# EVK-NORA-B2_SCHEM_0004_SWITCH_Memory.net
KiCad netlist of a schematic drawn in Altium Designer
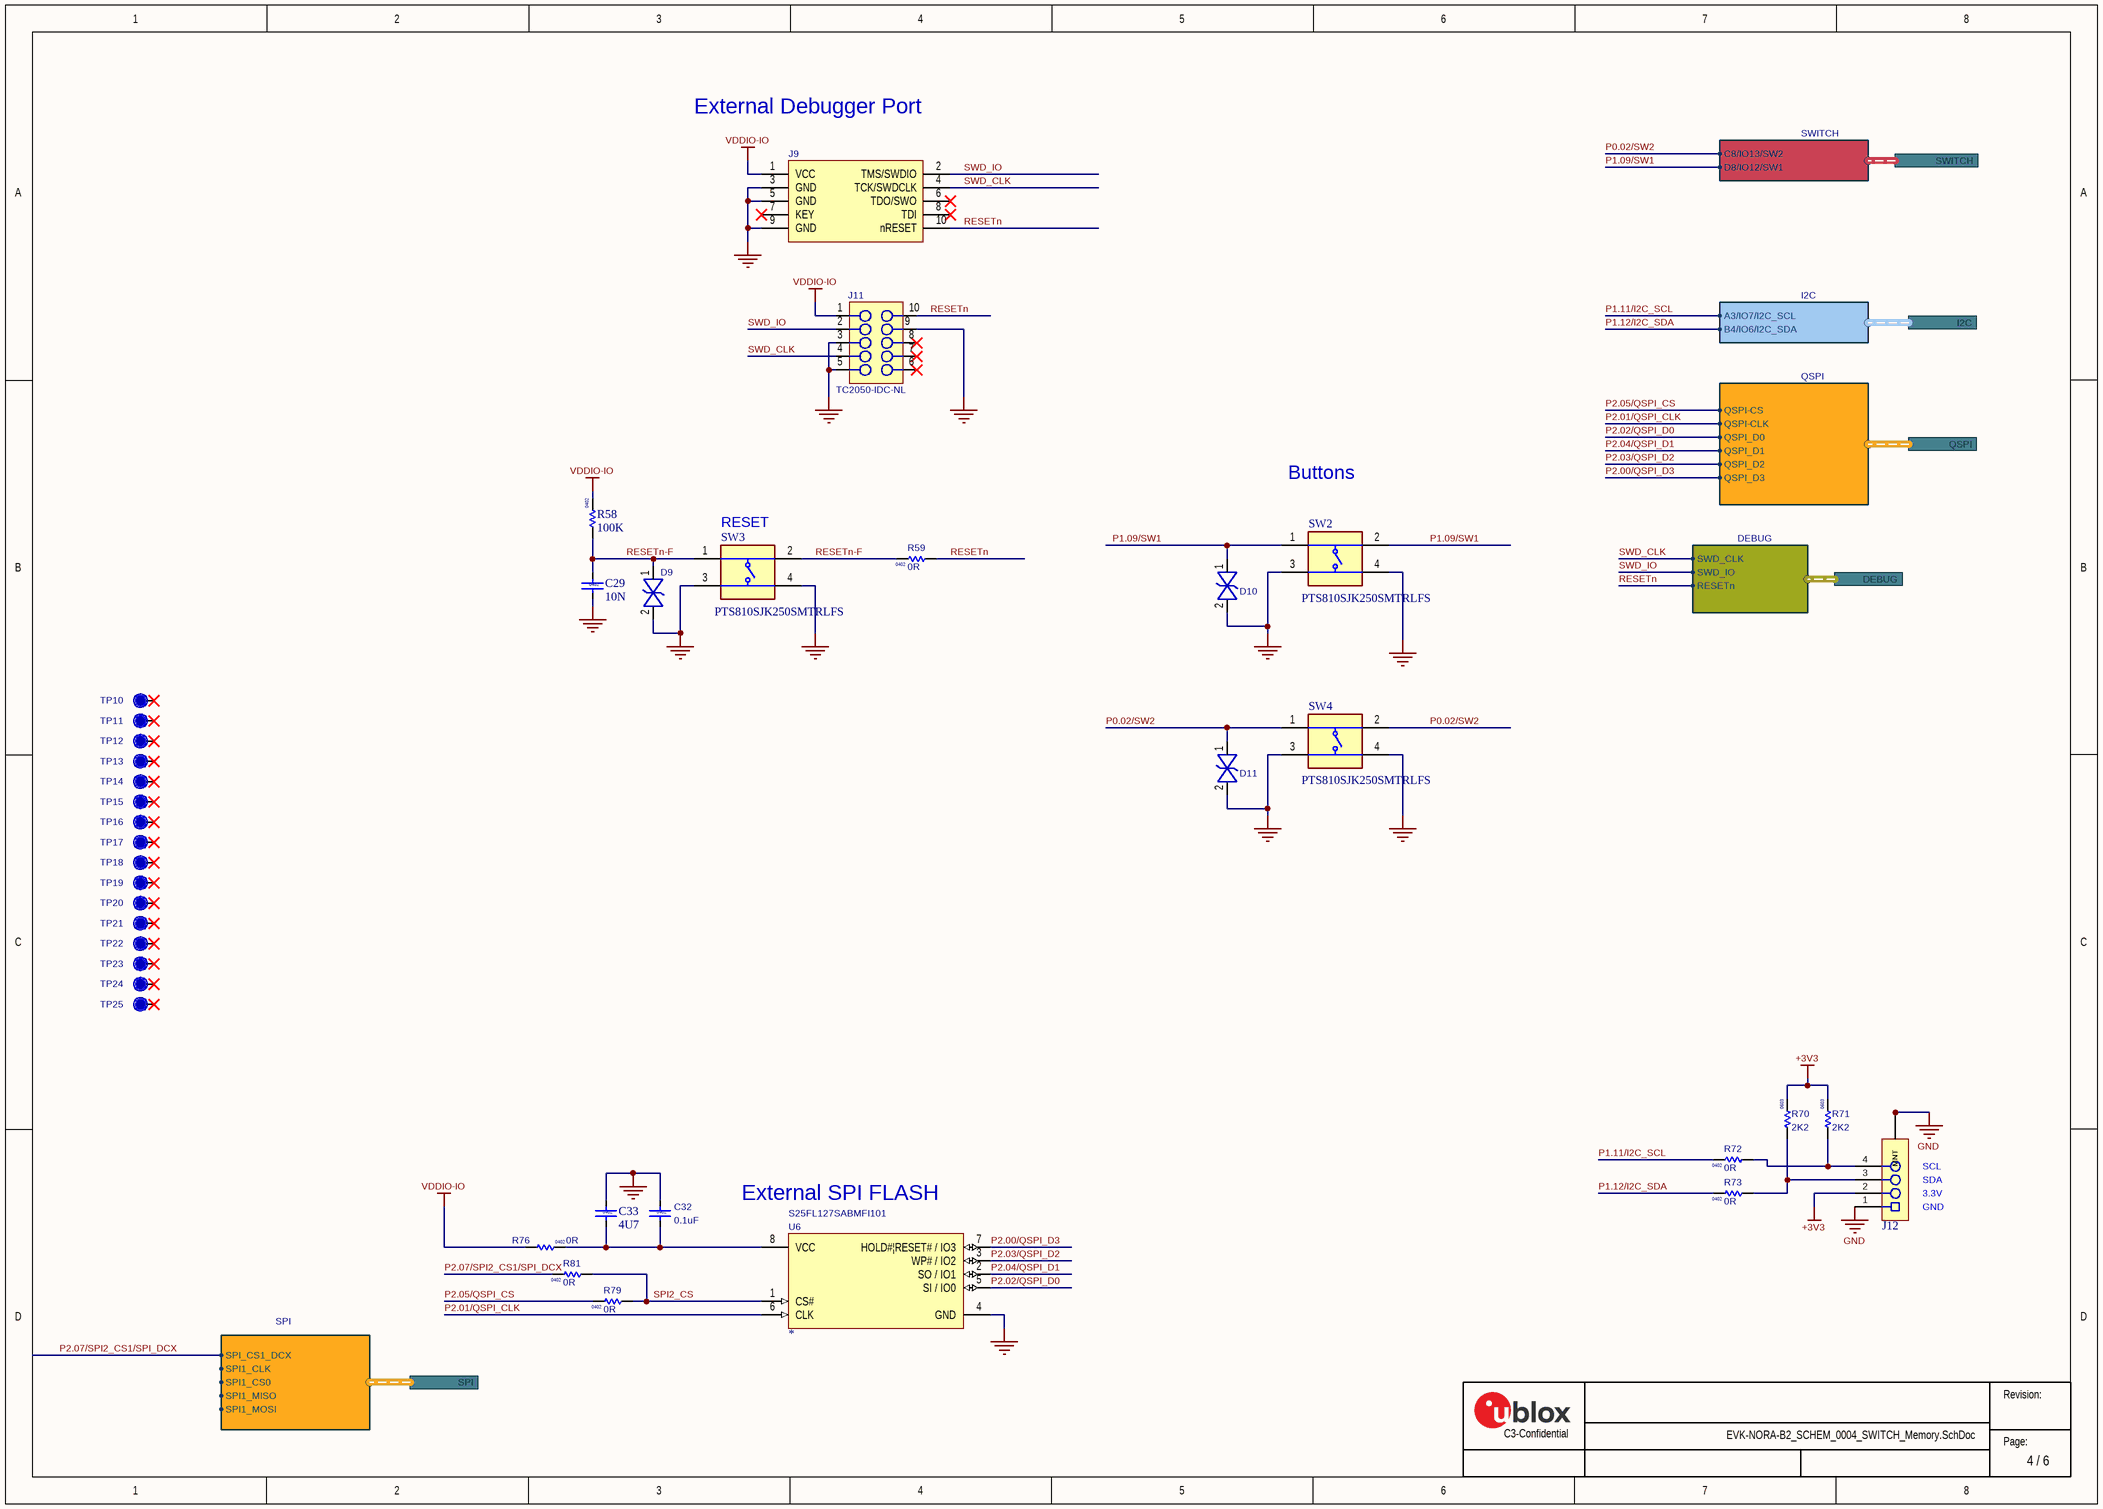
[diagram p0: EVK-NORA-B2_SCHEM_0004_SWITCH_Memory.SchDoc]

(export (version "E")
  (design (tool "Eeschema 10.0.6"))
  (components
    (comp (ref "C29")
      (value "10N")
      (footprint "Cap_0402_1100Lx600Wx600H_600x600Pad_350G_FLX")
      (description "CAP CER X7R 0402 10N 10% 16V")
      (fields
        (field (name "SIZE") "0402")
        (field (name "PART NUMBER") "UBXH01-0023025")
        (field (name "TOLERANCE") "10%")
        (field (name "EDITOR") "roland.rust")
        (field (name "RELEASED BY") "anthony.gergis")
      )
      (libsource (lib "UBX_Parts_DB_Lib") (part "Cap Chip"))
    )
    (comp (ref "C32")
      (value "0.1uF")
      (footprint "Cap 0402 HD")
      (description "Cap, Ceramic 0.1uF 10V 10% X5R 0402")
      (fields
        (field (name "SIZE") "0402")
        (field (name "PART NUMBER") "120-00016")
        (field (name "MANUFACTURER") "Murata Electronics North America")
      )
      (libsource (lib "Arena_Parts_DB_Lib") (part "Cap Chip"))
    )
    (comp (ref "C33")
      (value "4U7")
      (footprint "Cap 0402 HD")
      (description "CAP CER X5R 0402 4U7 20% 10V")
      (fields
        (field (name "SIZE") "0402")
        (field (name "PART NUMBER") "UBXH01-0000243")
        (field (name "TOLERANCE") "20%")
        (field (name "EDITOR") "martin.pilik")
        (field (name "RELEASED BY") "fabrice.bret-dibat")
      )
      (libsource (lib "UBX_Parts_DB_Lib") (part "Cap Chip"))
    )
    (comp (ref "D9")
      (value "110-00019")
      (footprint "SOD-923")
      (description "ESD9B3.3ST5G")
      (fields (field (name "MANUFACTURER") "ON Semiconductor") (field (name "VOLTAGE") "3.3V"))
      (libsource (lib "Arena_Parts_DB_Lib") (part "Diode_TVS"))
    )
    (comp (ref "D10")
      (value "110-00019")
      (footprint "SOD-923")
      (description "ESD9B3.3ST5G")
      (fields (field (name "MANUFACTURER") "ON Semiconductor") (field (name "VOLTAGE") "3.3V"))
      (libsource (lib "Arena_Parts_DB_Lib") (part "Diode_TVS"))
    )
    (comp (ref "D11")
      (value "110-00019")
      (footprint "SOD-923")
      (description "ESD9B3.3ST5G")
      (fields (field (name "MANUFACTURER") "ON Semiconductor") (field (name "VOLTAGE") "3.3V"))
      (libsource (lib "Arena_Parts_DB_Lib") (part "Diode_TVS"))
    )
    (comp (ref "J9")
      (value "130-00099")
      (footprint "HDR.050P-10Pin-2x5-SMT_Key")
      (description "Header 0.05\" 10Pin 2Row SMD Black")
      (fields (field (name "MANUFACTURER") "Samtec"))
      (libsource (lib "Arena_Parts_DB_Lib") (part "JTAG-10Pin"))
    )
    (comp (ref "J11")
      (value "TC2050-IDC-NLDNP")
      (footprint "TC2050-IDC-NL")
      (description "CON PADS FOR CBL PLUG-OF-NAILS 10-PIN NO LEGS")
      (fields
        (field (name "MANUFACTURER P/N") "TC2050-IDC-NL")
        (field (name "PART NUMBER") "TC2050-IDC-NL")
        (field (name "MANUFACTURER") "TAG Connect")
        (field (name "ADDED BY") "Paul B")
      )
      (libsource (lib "LEGACY_Rigado_AltiumLib") (part "CON-10Pin_2Row_ALT"))
    )
    (comp (ref "J12")
      (value "UBXH04-0000797")
      (footprint "SM04B-SRSS-TB")
      (description "CONN JST SH SERIES SMT 4 POS MALE 1MM RA 50V 1A")
      (fields
        (field (name "VOLTAGE") "None")
        (field (name "MANUFACTURER") "JST")
        (field (name "EDITOR") "eric.moog")
      )
      (libsource (lib "UBX_Parts_DB_Lib") (part "SM04B-SRSS-TB"))
    )
    (comp (ref "R58")
      (value "100K")
      (footprint "RES_0402_1100Lx600Wx400H_500x600Pad_400G_FLX")
      (description "RES THICK FILM CHIP 0402 100K 5% 100mW")
      (fields
        (field (name "SIZE") "0402")
        (field (name "PART NUMBER") "UBXH18-0008097")
        (field (name "TOLERANCE") "5%")
        (field (name "EDITOR") "roland.rust")
        (field (name "RELEASED BY") "roland.rust")
      )
      (libsource (lib "UBX_Parts_DB_Lib") (part "Res sm"))
    )
    (comp (ref "R59")
      (value "0R")
      (footprint "RES 0402 HD")
      (description "RES THICK FILM CHIP 0402 0R 0 100mW")
      (fields
        (field (name "SIZE") "0402")
        (field (name "PART NUMBER") "UBXH18-0003002")
        (field (name "TOLERANCE") "0")
        (field (name "EDITOR") "charlotte.biber")
        (field (name "RELEASED BY") "peter.mueller")
      )
      (libsource (lib "UBX_Parts_DB_Lib") (part "Res sm"))
    )
    (comp (ref "R70")
      (value "2K2")
      (footprint "RES_0603_1700Lx950Wx600H_600x1000Pad_800G_FLX")
      (description "RES THICK FILM CHIP 0603 2K2 5% 100mW")
      (fields
        (field (name "SIZE") "0603")
        (field (name "PART NUMBER") "UBXH18-0007081")
        (field (name "TOLERANCE") "5%")
        (field (name "EDITOR") "roland.rust")
        (field (name "RELEASED BY") "roland.rust")
      )
      (libsource (lib "UBX_Parts_DB_Lib") (part "Res sm"))
    )
    (comp (ref "R71")
      (value "2K2")
      (footprint "RES_0603_1700Lx950Wx600H_600x1000Pad_800G_FLX")
      (description "RES THICK FILM CHIP 0603 2K2 5% 100mW")
      (fields
        (field (name "SIZE") "0603")
        (field (name "PART NUMBER") "UBXH18-0007081")
        (field (name "TOLERANCE") "5%")
        (field (name "EDITOR") "roland.rust")
        (field (name "RELEASED BY") "roland.rust")
      )
      (libsource (lib "UBX_Parts_DB_Lib") (part "Res sm"))
    )
    (comp (ref "R72")
      (value "0R")
      (footprint "RES 0402 HD")
      (description "RES THICK FILM CHIP 0402 0R 0 100mW")
      (fields
        (field (name "SIZE") "0402")
        (field (name "PART NUMBER") "UBXH18-0003002")
        (field (name "TOLERANCE") "0")
        (field (name "EDITOR") "charlotte.biber")
        (field (name "RELEASED BY") "peter.mueller")
      )
      (libsource (lib "UBX_Parts_DB_Lib") (part "Res sm"))
    )
    (comp (ref "R73")
      (value "0R")
      (footprint "RES 0402 HD")
      (description "RES THICK FILM CHIP 0402 0R 0 100mW")
      (fields
        (field (name "SIZE") "0402")
        (field (name "PART NUMBER") "UBXH18-0003002")
        (field (name "TOLERANCE") "0")
        (field (name "EDITOR") "charlotte.biber")
        (field (name "RELEASED BY") "peter.mueller")
      )
      (libsource (lib "UBX_Parts_DB_Lib") (part "Res sm"))
    )
    (comp (ref "R76")
      (value "0R")
      (footprint "RES 0402 HD")
      (description "RES THICK FILM CHIP 0402 0R 0 100mW")
      (fields
        (field (name "SIZE") "0402")
        (field (name "PART NUMBER") "UBXH18-0003002")
        (field (name "TOLERANCE") "0")
        (field (name "EDITOR") "charlotte.biber")
        (field (name "RELEASED BY") "peter.mueller")
      )
      (libsource (lib "UBX_Parts_DB_Lib") (part "Res sm"))
    )
    (comp (ref "R79")
      (value "0R")
      (footprint "RES 0402 HD")
      (description "RES THICK FILM CHIP 0402 0R 0 100mW")
      (fields
        (field (name "SIZE") "0402")
        (field (name "PART NUMBER") "UBXH18-0003002")
        (field (name "TOLERANCE") "0")
        (field (name "EDITOR") "charlotte.biber")
        (field (name "RELEASED BY") "peter.mueller")
      )
      (libsource (lib "UBX_Parts_DB_Lib") (part "Res sm"))
    )
    (comp (ref "R81")
      (value "0R")
      (footprint "RES 0402 HD")
      (description "RES THICK FILM CHIP 0402 0R 0 100mW")
      (fields
        (field (name "SIZE") "0402")
        (field (name "PART NUMBER") "UBXH18-0003002")
        (field (name "TOLERANCE") "0")
        (field (name "EDITOR") "charlotte.biber")
        (field (name "RELEASED BY") "peter.mueller")
      )
      (libsource (lib "UBX_Parts_DB_Lib") (part "Res sm"))
    )
    (comp (ref "SW2")
      (value "PTS810SJK250SMTRLFS")
      (footprint "SamacSys:PTS810SJG250SMTRLFS")
      (description "Switch")
      (fields (field (name "MOUSER PART NUMBER") "611-PTS810SJK250SMTR"))
      (libsource (lib "SamacSys") (part "PTS810SJK250SMTRLFS"))
    )
    (comp (ref "SW3")
      (value "PTS810SJK250SMTRLFS")
      (footprint "SamacSys:PTS810SJG250SMTRLFS")
      (description "Switch")
      (fields (field (name "MOUSER PART NUMBER") "611-PTS810SJK250SMTR"))
      (libsource (lib "SamacSys") (part "PTS810SJK250SMTRLFS"))
    )
    (comp (ref "SW4")
      (value "PTS810SJK250SMTRLFS")
      (footprint "SamacSys:PTS810SJG250SMTRLFS")
      (description "Switch")
      (fields (field (name "MOUSER PART NUMBER") "611-PTS810SJK250SMTR"))
      (libsource (lib "SamacSys") (part "PTS810SJK250SMTRLFS"))
    )
    (comp (ref "TP10")
      (value "TP")
      (footprint "TP10R")
      (description "Testpoint, Round 1.0mm Dia")
      (fields
        (field (name "PART NUMBER") "TP10R")
        (field (name "ADDED BY") "Jeremy D")
        (field (name "CHECKED BY") "Paul B")
      )
      (libsource (lib "LEGACY_Rigado_AltiumLib") (part "TP_R"))
    )
    (comp (ref "TP11")
      (value "TP")
      (footprint "TP10R")
      (description "Testpoint, Round 1.0mm Dia")
      (fields
        (field (name "PART NUMBER") "TP10R")
        (field (name "ADDED BY") "Jeremy D")
        (field (name "CHECKED BY") "Paul B")
      )
      (libsource (lib "LEGACY_Rigado_AltiumLib") (part "TP_R"))
    )
    (comp (ref "TP12")
      (value "TP")
      (footprint "TP10R")
      (description "Testpoint, Round 1.0mm Dia")
      (fields
        (field (name "PART NUMBER") "TP10R")
        (field (name "ADDED BY") "Jeremy D")
        (field (name "CHECKED BY") "Paul B")
      )
      (libsource (lib "LEGACY_Rigado_AltiumLib") (part "TP_R"))
    )
    (comp (ref "TP13")
      (value "TP")
      (footprint "TP10R")
      (description "Testpoint, Round 1.0mm Dia")
      (fields
        (field (name "PART NUMBER") "TP10R")
        (field (name "ADDED BY") "Jeremy D")
        (field (name "CHECKED BY") "Paul B")
      )
      (libsource (lib "LEGACY_Rigado_AltiumLib") (part "TP_R"))
    )
    (comp (ref "TP14")
      (value "TP")
      (footprint "TP10R")
      (description "Testpoint, Round 1.0mm Dia")
      (fields
        (field (name "PART NUMBER") "TP10R")
        (field (name "ADDED BY") "Jeremy D")
        (field (name "CHECKED BY") "Paul B")
      )
      (libsource (lib "LEGACY_Rigado_AltiumLib") (part "TP_R"))
    )
    (comp (ref "TP15")
      (value "TP")
      (footprint "TP10R")
      (description "Testpoint, Round 1.0mm Dia")
      (fields
        (field (name "PART NUMBER") "TP10R")
        (field (name "ADDED BY") "Jeremy D")
        (field (name "CHECKED BY") "Paul B")
      )
      (libsource (lib "LEGACY_Rigado_AltiumLib") (part "TP_R"))
    )
    (comp (ref "TP16")
      (value "TP")
      (footprint "TP10R")
      (description "Testpoint, Round 1.0mm Dia")
      (fields
        (field (name "PART NUMBER") "TP10R")
        (field (name "ADDED BY") "Jeremy D")
        (field (name "CHECKED BY") "Paul B")
      )
      (libsource (lib "LEGACY_Rigado_AltiumLib") (part "TP_R"))
    )
    (comp (ref "TP17")
      (value "TP")
      (footprint "TP10R")
      (description "Testpoint, Round 1.0mm Dia")
      (fields
        (field (name "PART NUMBER") "TP10R")
        (field (name "ADDED BY") "Jeremy D")
        (field (name "CHECKED BY") "Paul B")
      )
      (libsource (lib "LEGACY_Rigado_AltiumLib") (part "TP_R"))
    )
    (comp (ref "TP18")
      (value "TP")
      (footprint "TP10R")
      (description "Testpoint, Round 1.0mm Dia")
      (fields
        (field (name "PART NUMBER") "TP10R")
        (field (name "ADDED BY") "Jeremy D")
        (field (name "CHECKED BY") "Paul B")
      )
      (libsource (lib "LEGACY_Rigado_AltiumLib") (part "TP_R"))
    )
    (comp (ref "TP19")
      (value "TP")
      (footprint "TP10R")
      (description "Testpoint, Round 1.0mm Dia")
      (fields
        (field (name "PART NUMBER") "TP10R")
        (field (name "ADDED BY") "Jeremy D")
        (field (name "CHECKED BY") "Paul B")
      )
      (libsource (lib "LEGACY_Rigado_AltiumLib") (part "TP_R"))
    )
    (comp (ref "TP20")
      (value "TP")
      (footprint "TP10R")
      (description "Testpoint, Round 1.0mm Dia")
      (fields
        (field (name "PART NUMBER") "TP10R")
        (field (name "ADDED BY") "Jeremy D")
        (field (name "CHECKED BY") "Paul B")
      )
      (libsource (lib "LEGACY_Rigado_AltiumLib") (part "TP_R"))
    )
    (comp (ref "TP21")
      (value "TP")
      (footprint "TP10R")
      (description "Testpoint, Round 1.0mm Dia")
      (fields
        (field (name "PART NUMBER") "TP10R")
        (field (name "ADDED BY") "Jeremy D")
        (field (name "CHECKED BY") "Paul B")
      )
      (libsource (lib "LEGACY_Rigado_AltiumLib") (part "TP_R"))
    )
    (comp (ref "TP22")
      (value "TP")
      (footprint "TP10R")
      (description "Testpoint, Round 1.0mm Dia")
      (fields
        (field (name "PART NUMBER") "TP10R")
        (field (name "ADDED BY") "Jeremy D")
        (field (name "CHECKED BY") "Paul B")
      )
      (libsource (lib "LEGACY_Rigado_AltiumLib") (part "TP_R"))
    )
    (comp (ref "TP23")
      (value "TP")
      (footprint "TP10R")
      (description "Testpoint, Round 1.0mm Dia")
      (fields
        (field (name "PART NUMBER") "TP10R")
        (field (name "ADDED BY") "Jeremy D")
        (field (name "CHECKED BY") "Paul B")
      )
      (libsource (lib "LEGACY_Rigado_AltiumLib") (part "TP_R"))
    )
    (comp (ref "TP24")
      (value "TP")
      (footprint "TP10R")
      (description "Testpoint, Round 1.0mm Dia")
      (fields
        (field (name "PART NUMBER") "TP10R")
        (field (name "ADDED BY") "Jeremy D")
        (field (name "CHECKED BY") "Paul B")
      )
      (libsource (lib "LEGACY_Rigado_AltiumLib") (part "TP_R"))
    )
    (comp (ref "TP25")
      (value "TP")
      (footprint "TP10R")
      (description "Testpoint, Round 1.0mm Dia")
      (fields
        (field (name "PART NUMBER") "TP10R")
        (field (name "ADDED BY") "Jeremy D")
        (field (name "CHECKED BY") "Paul B")
      )
      (libsource (lib "LEGACY_Rigado_AltiumLib") (part "TP_R"))
    )
    (comp (ref "U6")
      (value "240-00017")
      (footprint "SOIC-8W")
      (description "IC, Flash 128MBIT, 108MHz, 8SOIC")
      (fields
        (field (name "MANUFACTURER P/N") "*")
        (field (name "MANUFACTURER PART NUMBER 1") "S25FL127SABMFI101")
        (field (name "VOLTAGE") "3.6V")
      )
      (libsource (lib "Arena_Parts_DB_Lib") (part "SPI_Flash_Memory_8Pin"))
    )
  )
  (nets
    (net (code "6") (name "+3V3") (class "Default")
      (node (ref "J12") (pin "2") (pinfunction "2_2") (pintype "passive"))
      (node (ref "R70") (pin "2") (pinfunction "2_2") (pintype "passive"))
      (node (ref "R71") (pin "2") (pinfunction "2_2") (pintype "passive"))
    )
    (net (code "7") (name "/P0.02{slash}SW2") (class "Default")
      (node (ref "D11") (pin "1") (pintype "passive"))
      (node (ref "SW4") (pin "1") (pinfunction "1_1") (pintype "passive"))
      (node (ref "SW4") (pin "2") (pinfunction "2_2") (pintype "passive"))
    )
    (net (code "8") (name "/P1.09{slash}SW1") (class "Default")
      (node (ref "D10") (pin "1") (pintype "passive"))
      (node (ref "SW2") (pin "1") (pinfunction "1_1") (pintype "passive"))
      (node (ref "SW2") (pin "2") (pinfunction "2_2") (pintype "passive"))
    )
    (net (code "9") (name "/P1.11{slash}I2C_SCL") (class "Default")
      (node (ref "R72") (pin "2") (pinfunction "2_2") (pintype "passive"))
    )
    (net (code "10") (name "/P1.12{slash}I2C_SDA") (class "Default")
      (node (ref "R73") (pin "2") (pinfunction "2_2") (pintype "passive"))
    )
    (net (code "11") (name "/P2.00{slash}QSPI_D3") (class "Default")
      (node (ref "U6") (pin "7") (pinfunction "HOLD#¦RESET#_/_IO3_7") (pintype "bidirectional"))
    )
    (net (code "12") (name "/P2.01{slash}QSPI_CLK") (class "Default")
      (node (ref "U6") (pin "6") (pinfunction "CLK_6") (pintype "input"))
    )
    (net (code "13") (name "/P2.02{slash}QSPI_D0") (class "Default")
      (node (ref "U6") (pin "5") (pinfunction "SI_/_IO0_5") (pintype "bidirectional"))
    )
    (net (code "14") (name "/P2.03{slash}QSPI_D2") (class "Default")
      (node (ref "U6") (pin "3") (pinfunction "WP#_/_IO2_3") (pintype "bidirectional"))
    )
    (net (code "15") (name "/P2.04{slash}QSPI_D1") (class "Default")
      (node (ref "U6") (pin "2") (pinfunction "SO_/_IO1_2") (pintype "bidirectional"))
    )
    (net (code "16") (name "/P2.05{slash}QSPI_CS") (class "Default")
      (node (ref "R79") (pin "2") (pinfunction "2_2") (pintype "passive"))
    )
    (net (code "17") (name "/P2.07{slash}SPI2_CS1{slash}SPI_DCX") (class "Default")
      (node (ref "R81") (pin "2") (pinfunction "2_2") (pintype "passive"))
    )
    (net (code "18") (name "/RESETn") (class "Default")
      (node (ref "J11") (pin "10") (pintype "passive"))
      (node (ref "J9") (pin "10") (pinfunction "nRESET_10") (pintype "passive"))
      (node (ref "R59") (pin "1") (pinfunction "1_1") (pintype "passive"))
    )
    (net (code "19") (name "/RESETn-F") (class "Default")
      (node (ref "C29") (pin "1") (pinfunction "1_1") (pintype "passive"))
      (node (ref "D9") (pin "1") (pintype "passive"))
      (node (ref "R58") (pin "1") (pinfunction "1_1") (pintype "passive"))
      (node (ref "R59") (pin "2") (pinfunction "2_2") (pintype "passive"))
      (node (ref "SW3") (pin "1") (pinfunction "1_1") (pintype "passive"))
      (node (ref "SW3") (pin "2") (pinfunction "2_2") (pintype "passive"))
    )
    (net (code "20") (name "/SPI2_CS") (class "Default")
      (node (ref "R79") (pin "1") (pinfunction "1_1") (pintype "passive"))
      (node (ref "R81") (pin "1") (pinfunction "1_1") (pintype "passive"))
      (node (ref "U6") (pin "1") (pinfunction "CS#_1") (pintype "input"))
    )
    (net (code "21") (name "/SWD_CLK") (class "Default")
      (node (ref "J11") (pin "4") (pintype "passive"))
      (node (ref "J9") (pin "4") (pinfunction "TCK/SWDCLK_4") (pintype "passive"))
    )
    (net (code "22") (name "/SWD_IO") (class "Default")
      (node (ref "J11") (pin "2") (pintype "passive"))
      (node (ref "J9") (pin "2") (pinfunction "TMS/SWDIO_2") (pintype "passive"))
    )
    (net (code "28") (name "GND") (class "Default")
      (node (ref "C29") (pin "2") (pinfunction "2_2") (pintype "passive"))
      (node (ref "C32") (pin "1") (pinfunction "1_1") (pintype "passive"))
      (node (ref "C33") (pin "1") (pinfunction "1_1") (pintype "passive"))
      (node (ref "D10") (pin "2") (pintype "passive"))
      (node (ref "D11") (pin "2") (pintype "passive"))
      (node (ref "D9") (pin "2") (pintype "passive"))
      (node (ref "J11") (pin "3") (pintype "passive"))
      (node (ref "J11") (pin "5") (pintype "passive"))
      (node (ref "J12") (pin "1") (pinfunction "1_1") (pintype "passive"))
      (node (ref "J12") (pin "M1") (pinfunction "MNT_M1") (pintype "passive"))
      (node (ref "J12") (pin "M2") (pinfunction "MNT_M2") (pintype "passive"))
      (node (ref "J9") (pin "3") (pinfunction "GND_3") (pintype "passive"))
      (node (ref "J9") (pin "5") (pinfunction "GND_5") (pintype "passive"))
      (node (ref "J9") (pin "9") (pinfunction "GND_9") (pintype "passive"))
      (node (ref "SW2") (pin "3") (pinfunction "3_3") (pintype "passive"))
      (node (ref "SW2") (pin "4") (pinfunction "4_4") (pintype "passive"))
      (node (ref "SW3") (pin "3") (pinfunction "3_3") (pintype "passive"))
      (node (ref "SW3") (pin "4") (pinfunction "4_4") (pintype "passive"))
      (node (ref "SW4") (pin "3") (pinfunction "3_3") (pintype "passive"))
      (node (ref "SW4") (pin "4") (pinfunction "4_4") (pintype "passive"))
      (node (ref "U6") (pin "4") (pinfunction "GND_4") (pintype "power_in"))
    )
    (net (code "29") (name "Net-(J12-Pad3)") (class "Default")
      (node (ref "J12") (pin "3") (pinfunction "3_3") (pintype "passive"))
      (node (ref "R70") (pin "1") (pinfunction "1_1") (pintype "passive"))
      (node (ref "R73") (pin "1") (pinfunction "1_1") (pintype "passive"))
    )
    (net (code "30") (name "Net-(J12-Pad4)") (class "Default")
      (node (ref "J12") (pin "4") (pinfunction "4_4") (pintype "passive"))
      (node (ref "R71") (pin "1") (pinfunction "1_1") (pintype "passive"))
      (node (ref "R72") (pin "1") (pinfunction "1_1") (pintype "passive"))
    )
    (net (code "31") (name "Net-(U6-VCC)") (class "Default")
      (node (ref "C32") (pin "2") (pinfunction "2_2") (pintype "passive"))
      (node (ref "C33") (pin "2") (pinfunction "2_2") (pintype "passive"))
      (node (ref "R76") (pin "2") (pinfunction "2_2") (pintype "passive"))
      (node (ref "U6") (pin "8") (pinfunction "VCC_8") (pintype "power_in"))
    )
    (net (code "32") (name "VDDIO-IO") (class "Default")
      (node (ref "J11") (pin "1") (pintype "passive"))
      (node (ref "J9") (pin "1") (pinfunction "VCC_1") (pintype "passive"))
      (node (ref "R58") (pin "2") (pinfunction "2_2") (pintype "passive"))
      (node (ref "R76") (pin "1") (pinfunction "1_1") (pintype "passive"))
    )
    (net (code "33") (name "unconnected-(J9-KEY-Pad7)") (class "Default")
      (node (ref "J9") (pin "7") (pinfunction "KEY_7") (pintype "passive+no_connect"))
    )
    (net (code "34") (name "unconnected-(J9-TDI-Pad8)") (class "Default")
      (node (ref "J9") (pin "8") (pinfunction "TDI_8") (pintype "passive+no_connect"))
    )
    (net (code "35") (name "unconnected-(J9-TDO{slash}SWO-Pad6)") (class "Default")
      (node (ref "J9") (pin "6") (pinfunction "TDO/SWO_6") (pintype "passive+no_connect"))
    )
    (net (code "36") (name "unconnected-(J11-Pad6)") (class "Default")
      (node (ref "J11") (pin "6") (pintype "passive+no_connect"))
    )
    (net (code "37") (name "unconnected-(J11-Pad7)") (class "Default")
      (node (ref "J11") (pin "7") (pintype "passive+no_connect"))
    )
    (net (code "38") (name "unconnected-(J11-Pad8)") (class "Default")
      (node (ref "J11") (pin "8") (pintype "passive+no_connect"))
    )
    (net (code "39") (name "unconnected-(J11-Pad9)") (class "Default")
      (node (ref "J11") (pin "9") (pintype "passive"))
    )
    (net (code "40") (name "unconnected-(TP10-Pad1)") (class "Default")
      (node (ref "TP10") (pin "1") (pintype "passive+no_connect"))
    )
    (net (code "41") (name "unconnected-(TP11-Pad1)") (class "Default")
      (node (ref "TP11") (pin "1") (pintype "passive+no_connect"))
    )
    (net (code "42") (name "unconnected-(TP12-Pad1)") (class "Default")
      (node (ref "TP12") (pin "1") (pintype "passive+no_connect"))
    )
    (net (code "43") (name "unconnected-(TP13-Pad1)") (class "Default")
      (node (ref "TP13") (pin "1") (pintype "passive+no_connect"))
    )
    (net (code "44") (name "unconnected-(TP14-Pad1)") (class "Default")
      (node (ref "TP14") (pin "1") (pintype "passive+no_connect"))
    )
    (net (code "45") (name "unconnected-(TP15-Pad1)") (class "Default")
      (node (ref "TP15") (pin "1") (pintype "passive+no_connect"))
    )
    (net (code "46") (name "unconnected-(TP16-Pad1)") (class "Default")
      (node (ref "TP16") (pin "1") (pintype "passive+no_connect"))
    )
    (net (code "47") (name "unconnected-(TP17-Pad1)") (class "Default")
      (node (ref "TP17") (pin "1") (pintype "passive+no_connect"))
    )
    (net (code "48") (name "unconnected-(TP18-Pad1)") (class "Default")
      (node (ref "TP18") (pin "1") (pintype "passive+no_connect"))
    )
    (net (code "49") (name "unconnected-(TP19-Pad1)") (class "Default")
      (node (ref "TP19") (pin "1") (pintype "passive+no_connect"))
    )
    (net (code "50") (name "unconnected-(TP20-Pad1)") (class "Default")
      (node (ref "TP20") (pin "1") (pintype "passive+no_connect"))
    )
    (net (code "51") (name "unconnected-(TP21-Pad1)") (class "Default")
      (node (ref "TP21") (pin "1") (pintype "passive+no_connect"))
    )
    (net (code "52") (name "unconnected-(TP22-Pad1)") (class "Default")
      (node (ref "TP22") (pin "1") (pintype "passive+no_connect"))
    )
    (net (code "53") (name "unconnected-(TP23-Pad1)") (class "Default")
      (node (ref "TP23") (pin "1") (pintype "passive+no_connect"))
    )
    (net (code "54") (name "unconnected-(TP24-Pad1)") (class "Default")
      (node (ref "TP24") (pin "1") (pintype "passive+no_connect"))
    )
    (net (code "55") (name "unconnected-(TP25-Pad1)") (class "Default")
      (node (ref "TP25") (pin "1") (pintype "passive+no_connect"))
    )
  )
)
